# IN_12A.net
KiCad netlist of a schematic drawn in Altium Designer
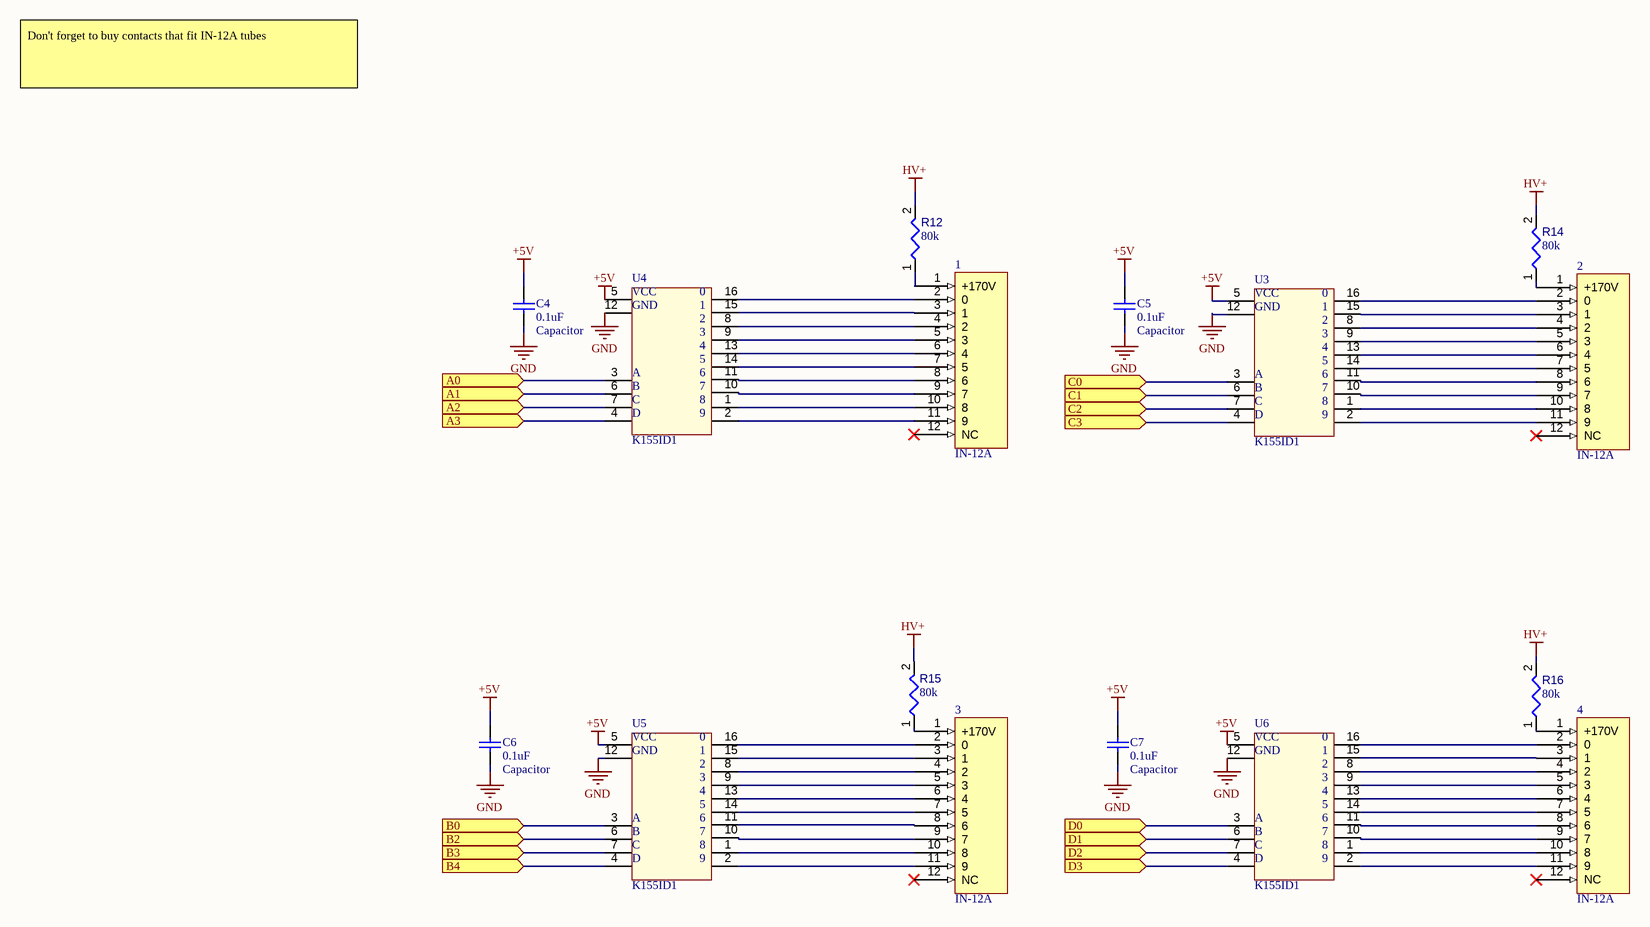
[diagram p0: IN_12A.SchDoc]

(export (version "E")
  (design (tool "Eeschema 10.0.6"))
  (components
    (comp (ref "1") (value "IN-12A") (footprint "IN-12A") (libsource (lib "HV_LIB") (part "IN-12A")))
    (comp (ref "2") (value "IN-12A") (footprint "IN-12A") (libsource (lib "HV_LIB") (part "IN-12A")))
    (comp (ref "3") (value "IN-12A") (footprint "IN-12A") (libsource (lib "HV_LIB") (part "IN-12A")))
    (comp (ref "4") (value "IN-12A") (footprint "IN-12A") (libsource (lib "HV_LIB") (part "IN-12A")))
    (comp (ref "C4")
      (value "0.1uF")
      (footprint "FOOTPRINT-1206-GEN")
      (description "CAP CER 0.1UF 50V X7R 1206")
      (fields
        (field (name "PART NUMBER") "1276-7034-1-ND")
        (field (name "TYPE") "Capacitor")
        (field (name "Comment") "Capacitor - 0.1uF - 1206")
        (field (name "PUBLISHER") "Altium Limited")
      )
      (libsource (lib "University of California Riverside - FSAE") (part "Symbol"))
    )
    (comp (ref "C5")
      (value "0.1uF")
      (footprint "FOOTPRINT-1206-GEN")
      (description "CAP CER 0.1UF 50V X7R 1206")
      (fields
        (field (name "PART NUMBER") "1276-7034-1-ND")
        (field (name "TYPE") "Capacitor")
        (field (name "Comment") "Capacitor - 0.1uF - 1206")
        (field (name "PUBLISHER") "Altium Limited")
      )
      (libsource (lib "University of California Riverside - FSAE") (part "Symbol"))
    )
    (comp (ref "C6")
      (value "0.1uF")
      (footprint "FOOTPRINT-1206-GEN")
      (description "CAP CER 0.1UF 50V X7R 1206")
      (fields
        (field (name "PART NUMBER") "1276-7034-1-ND")
        (field (name "TYPE") "Capacitor")
        (field (name "Comment") "Capacitor - 0.1uF - 1206")
        (field (name "PUBLISHER") "Altium Limited")
      )
      (libsource (lib "University of California Riverside - FSAE") (part "Symbol"))
    )
    (comp (ref "C7")
      (value "0.1uF")
      (footprint "FOOTPRINT-1206-GEN")
      (description "CAP CER 0.1UF 50V X7R 1206")
      (fields
        (field (name "PART NUMBER") "1276-7034-1-ND")
        (field (name "TYPE") "Capacitor")
        (field (name "Comment") "Capacitor - 0.1uF - 1206")
        (field (name "PUBLISHER") "Altium Limited")
      )
      (libsource (lib "University of California Riverside - FSAE") (part "Symbol"))
    )
    (comp (ref "R12")
      (value "80k")
      (footprint "RESC3216X60X45ML15T20")
      (description "Chip Resistor, 80 KOhm, +/- 1%, 0.25 W, -55 to 155 degC, 1206 (3216 Metric)")
      (fields (field (name "POWER") "250mW") (field (name "TOLERANCE") "1%"))
      (libsource (lib "University of California Riverside - FSAE") (part "RES-2"))
    )
    (comp (ref "R14")
      (value "80k")
      (footprint "RESC3216X60X45ML15T20")
      (description "Chip Resistor, 80 KOhm, +/- 1%, 0.25 W, -55 to 155 degC, 1206 (3216 Metric)")
      (fields (field (name "POWER") "250mW") (field (name "TOLERANCE") "1%"))
      (libsource (lib "University of California Riverside - FSAE") (part "RES-2"))
    )
    (comp (ref "R15")
      (value "80k")
      (footprint "RESC3216X60X45ML15T20")
      (description "Chip Resistor, 80 KOhm, +/- 1%, 0.25 W, -55 to 155 degC, 1206 (3216 Metric)")
      (fields (field (name "POWER") "250mW") (field (name "TOLERANCE") "1%"))
      (libsource (lib "University of California Riverside - FSAE") (part "RES-2"))
    )
    (comp (ref "R16")
      (value "80k")
      (footprint "RESC3216X60X45ML15T20")
      (description "Chip Resistor, 80 KOhm, +/- 1%, 0.25 W, -55 to 155 degC, 1206 (3216 Metric)")
      (fields (field (name "POWER") "250mW") (field (name "TOLERANCE") "1%"))
      (libsource (lib "University of California Riverside - FSAE") (part "RES-2"))
    )
    (comp (ref "U3")
      (value "K155ID1")
      (footprint "Socket_DIP_16")
      (libsource (lib "HV_LIB") (part "K155ID1"))
    )
    (comp (ref "U4")
      (value "K155ID1")
      (footprint "Socket_DIP_16")
      (libsource (lib "HV_LIB") (part "K155ID1"))
    )
    (comp (ref "U5")
      (value "K155ID1")
      (footprint "Socket_DIP_16")
      (libsource (lib "HV_LIB") (part "K155ID1"))
    )
    (comp (ref "U6")
      (value "K155ID1")
      (footprint "Socket_DIP_16")
      (libsource (lib "HV_LIB") (part "K155ID1"))
    )
  )
  (nets
    (net (code "1") (name "+5V") (class "Default")
      (node (ref "C4") (pin "2") (pinfunction "2_2") (pintype "passive"))
      (node (ref "C5") (pin "2") (pinfunction "2_2") (pintype "passive"))
      (node (ref "C6") (pin "2") (pinfunction "2_2") (pintype "passive"))
      (node (ref "C7") (pin "2") (pinfunction "2_2") (pintype "passive"))
      (node (ref "U3") (pin "5") (pinfunction "5_5") (pintype "passive"))
      (node (ref "U4") (pin "5") (pinfunction "5_5") (pintype "passive"))
      (node (ref "U5") (pin "5") (pinfunction "5_5") (pintype "passive"))
      (node (ref "U6") (pin "5") (pinfunction "5_5") (pintype "passive"))
    )
    (net (code "2") (name "/A0") (class "Default")
      (node (ref "U4") (pin "3") (pinfunction "3_3") (pintype "passive"))
    )
    (net (code "3") (name "/A1") (class "Default")
      (node (ref "U4") (pin "6") (pinfunction "6_6") (pintype "passive"))
    )
    (net (code "4") (name "/A2") (class "Default")
      (node (ref "U4") (pin "7") (pinfunction "7_7") (pintype "passive"))
    )
    (net (code "5") (name "/A3") (class "Default")
      (node (ref "U4") (pin "4") (pinfunction "4_4") (pintype "passive"))
    )
    (net (code "6") (name "/B0") (class "Default")
      (node (ref "U5") (pin "3") (pinfunction "3_3") (pintype "passive"))
    )
    (net (code "7") (name "/B2") (class "Default")
      (node (ref "U5") (pin "6") (pinfunction "6_6") (pintype "passive"))
    )
    (net (code "8") (name "/B3") (class "Default")
      (node (ref "U5") (pin "7") (pinfunction "7_7") (pintype "passive"))
    )
    (net (code "9") (name "/B4") (class "Default")
      (node (ref "U5") (pin "4") (pinfunction "4_4") (pintype "passive"))
    )
    (net (code "10") (name "/C0") (class "Default")
      (node (ref "U3") (pin "3") (pinfunction "3_3") (pintype "passive"))
    )
    (net (code "11") (name "/C1") (class "Default")
      (node (ref "U3") (pin "6") (pinfunction "6_6") (pintype "passive"))
    )
    (net (code "12") (name "/C2") (class "Default")
      (node (ref "U3") (pin "7") (pinfunction "7_7") (pintype "passive"))
    )
    (net (code "13") (name "/C3") (class "Default")
      (node (ref "U3") (pin "4") (pinfunction "4_4") (pintype "passive"))
    )
    (net (code "14") (name "/D0") (class "Default")
      (node (ref "U6") (pin "3") (pinfunction "3_3") (pintype "passive"))
    )
    (net (code "15") (name "/D1") (class "Default")
      (node (ref "U6") (pin "6") (pinfunction "6_6") (pintype "passive"))
    )
    (net (code "16") (name "/D2") (class "Default")
      (node (ref "U6") (pin "7") (pinfunction "7_7") (pintype "passive"))
    )
    (net (code "17") (name "/D3") (class "Default")
      (node (ref "U6") (pin "4") (pinfunction "4_4") (pintype "passive"))
    )
    (net (code "18") (name "GND") (class "Default")
      (node (ref "C4") (pin "1") (pinfunction "1_1") (pintype "passive"))
      (node (ref "C5") (pin "1") (pinfunction "1_1") (pintype "passive"))
      (node (ref "C6") (pin "1") (pinfunction "1_1") (pintype "passive"))
      (node (ref "C7") (pin "1") (pinfunction "1_1") (pintype "passive"))
      (node (ref "U3") (pin "12") (pinfunction "12_12") (pintype "passive"))
      (node (ref "U4") (pin "12") (pinfunction "12_12") (pintype "passive"))
      (node (ref "U5") (pin "12") (pinfunction "12_12") (pintype "passive"))
      (node (ref "U6") (pin "12") (pinfunction "12_12") (pintype "passive"))
    )
    (net (code "19") (name "HV+") (class "Default")
      (node (ref "R12") (pin "2") (pinfunction "2_2") (pintype "passive"))
      (node (ref "R14") (pin "2") (pinfunction "2_2") (pintype "passive"))
      (node (ref "R15") (pin "2") (pinfunction "2_2") (pintype "passive"))
      (node (ref "R16") (pin "2") (pinfunction "2_2") (pintype "passive"))
    )
    (net (code "20") (name "Net-(1-+170V)") (class "Default")
      (node (ref "1") (pin "1") (pinfunction "+170V_1") (pintype "input"))
      (node (ref "R12") (pin "1") (pinfunction "1_1") (pintype "passive"))
    )
    (net (code "21") (name "Net-(1-0)") (class "Default")
      (node (ref "1") (pin "2") (pinfunction "0_2") (pintype "input"))
      (node (ref "U4") (pin "16") (pinfunction "16_16") (pintype "passive"))
    )
    (net (code "22") (name "Net-(1-1)") (class "Default")
      (node (ref "1") (pin "3") (pinfunction "1_3") (pintype "input"))
      (node (ref "U4") (pin "15") (pinfunction "15_15") (pintype "passive"))
    )
    (net (code "23") (name "Net-(1-2)") (class "Default")
      (node (ref "1") (pin "4") (pinfunction "2_4") (pintype "input"))
      (node (ref "U4") (pin "8") (pinfunction "8_8") (pintype "passive"))
    )
    (net (code "24") (name "Net-(1-3)") (class "Default")
      (node (ref "1") (pin "5") (pinfunction "3_5") (pintype "input"))
      (node (ref "U4") (pin "9") (pinfunction "9_9") (pintype "passive"))
    )
    (net (code "25") (name "Net-(1-4)") (class "Default")
      (node (ref "1") (pin "6") (pinfunction "4_6") (pintype "input"))
      (node (ref "U4") (pin "13") (pinfunction "13_13") (pintype "passive"))
    )
    (net (code "26") (name "Net-(1-5)") (class "Default")
      (node (ref "1") (pin "7") (pinfunction "5_7") (pintype "input"))
      (node (ref "U4") (pin "14") (pinfunction "14_14") (pintype "passive"))
    )
    (net (code "27") (name "Net-(1-6)") (class "Default")
      (node (ref "1") (pin "8") (pinfunction "6_8") (pintype "input"))
      (node (ref "U4") (pin "11") (pinfunction "11_11") (pintype "passive"))
    )
    (net (code "28") (name "Net-(1-7)") (class "Default")
      (node (ref "1") (pin "9") (pinfunction "7_9") (pintype "input"))
      (node (ref "U4") (pin "10") (pinfunction "10_10") (pintype "passive"))
    )
    (net (code "29") (name "Net-(1-8)") (class "Default")
      (node (ref "1") (pin "10") (pinfunction "8_10") (pintype "input"))
      (node (ref "U4") (pin "1") (pinfunction "1_1") (pintype "passive"))
    )
    (net (code "30") (name "Net-(1-9)") (class "Default")
      (node (ref "1") (pin "11") (pinfunction "9_11") (pintype "input"))
      (node (ref "U4") (pin "2") (pinfunction "2_2") (pintype "passive"))
    )
    (net (code "31") (name "Net-(2-+170V)") (class "Default")
      (node (ref "2") (pin "1") (pinfunction "+170V_1") (pintype "input"))
      (node (ref "R14") (pin "1") (pinfunction "1_1") (pintype "passive"))
    )
    (net (code "32") (name "Net-(2-0)") (class "Default")
      (node (ref "2") (pin "2") (pinfunction "0_2") (pintype "input"))
      (node (ref "U3") (pin "16") (pinfunction "16_16") (pintype "passive"))
    )
    (net (code "33") (name "Net-(2-1)") (class "Default")
      (node (ref "2") (pin "3") (pinfunction "1_3") (pintype "input"))
      (node (ref "U3") (pin "15") (pinfunction "15_15") (pintype "passive"))
    )
    (net (code "34") (name "Net-(2-2)") (class "Default")
      (node (ref "2") (pin "4") (pinfunction "2_4") (pintype "input"))
      (node (ref "U3") (pin "8") (pinfunction "8_8") (pintype "passive"))
    )
    (net (code "35") (name "Net-(2-3)") (class "Default")
      (node (ref "2") (pin "5") (pinfunction "3_5") (pintype "input"))
      (node (ref "U3") (pin "9") (pinfunction "9_9") (pintype "passive"))
    )
    (net (code "36") (name "Net-(2-4)") (class "Default")
      (node (ref "2") (pin "6") (pinfunction "4_6") (pintype "input"))
      (node (ref "U3") (pin "13") (pinfunction "13_13") (pintype "passive"))
    )
    (net (code "37") (name "Net-(2-5)") (class "Default")
      (node (ref "2") (pin "7") (pinfunction "5_7") (pintype "input"))
      (node (ref "U3") (pin "14") (pinfunction "14_14") (pintype "passive"))
    )
    (net (code "38") (name "Net-(2-6)") (class "Default")
      (node (ref "2") (pin "8") (pinfunction "6_8") (pintype "input"))
      (node (ref "U3") (pin "11") (pinfunction "11_11") (pintype "passive"))
    )
    (net (code "39") (name "Net-(2-7)") (class "Default")
      (node (ref "2") (pin "9") (pinfunction "7_9") (pintype "input"))
      (node (ref "U3") (pin "10") (pinfunction "10_10") (pintype "passive"))
    )
    (net (code "40") (name "Net-(2-8)") (class "Default")
      (node (ref "2") (pin "10") (pinfunction "8_10") (pintype "input"))
      (node (ref "U3") (pin "1") (pinfunction "1_1") (pintype "passive"))
    )
    (net (code "41") (name "Net-(2-9)") (class "Default")
      (node (ref "2") (pin "11") (pinfunction "9_11") (pintype "input"))
      (node (ref "U3") (pin "2") (pinfunction "2_2") (pintype "passive"))
    )
    (net (code "42") (name "Net-(3-+170V)") (class "Default")
      (node (ref "3") (pin "1") (pinfunction "+170V_1") (pintype "input"))
      (node (ref "R15") (pin "1") (pinfunction "1_1") (pintype "passive"))
    )
    (net (code "43") (name "Net-(3-0)") (class "Default")
      (node (ref "3") (pin "2") (pinfunction "0_2") (pintype "input"))
      (node (ref "U5") (pin "16") (pinfunction "16_16") (pintype "passive"))
    )
    (net (code "44") (name "Net-(3-1)") (class "Default")
      (node (ref "3") (pin "3") (pinfunction "1_3") (pintype "input"))
      (node (ref "U5") (pin "15") (pinfunction "15_15") (pintype "passive"))
    )
    (net (code "45") (name "Net-(3-2)") (class "Default")
      (node (ref "3") (pin "4") (pinfunction "2_4") (pintype "input"))
      (node (ref "U5") (pin "8") (pinfunction "8_8") (pintype "passive"))
    )
    (net (code "46") (name "Net-(3-3)") (class "Default")
      (node (ref "3") (pin "5") (pinfunction "3_5") (pintype "input"))
      (node (ref "U5") (pin "9") (pinfunction "9_9") (pintype "passive"))
    )
    (net (code "47") (name "Net-(3-4)") (class "Default")
      (node (ref "3") (pin "6") (pinfunction "4_6") (pintype "input"))
      (node (ref "U5") (pin "13") (pinfunction "13_13") (pintype "passive"))
    )
    (net (code "48") (name "Net-(3-5)") (class "Default")
      (node (ref "3") (pin "7") (pinfunction "5_7") (pintype "input"))
      (node (ref "U5") (pin "14") (pinfunction "14_14") (pintype "passive"))
    )
    (net (code "49") (name "Net-(3-6)") (class "Default")
      (node (ref "3") (pin "8") (pinfunction "6_8") (pintype "input"))
      (node (ref "U5") (pin "11") (pinfunction "11_11") (pintype "passive"))
    )
    (net (code "50") (name "Net-(3-7)") (class "Default")
      (node (ref "3") (pin "9") (pinfunction "7_9") (pintype "input"))
      (node (ref "U5") (pin "10") (pinfunction "10_10") (pintype "passive"))
    )
    (net (code "51") (name "Net-(3-8)") (class "Default")
      (node (ref "3") (pin "10") (pinfunction "8_10") (pintype "input"))
      (node (ref "U5") (pin "1") (pinfunction "1_1") (pintype "passive"))
    )
    (net (code "52") (name "Net-(3-9)") (class "Default")
      (node (ref "3") (pin "11") (pinfunction "9_11") (pintype "input"))
      (node (ref "U5") (pin "2") (pinfunction "2_2") (pintype "passive"))
    )
    (net (code "53") (name "Net-(4-+170V)") (class "Default")
      (node (ref "4") (pin "1") (pinfunction "+170V_1") (pintype "input"))
      (node (ref "R16") (pin "1") (pinfunction "1_1") (pintype "passive"))
    )
    (net (code "54") (name "Net-(4-0)") (class "Default")
      (node (ref "4") (pin "2") (pinfunction "0_2") (pintype "input"))
      (node (ref "U6") (pin "16") (pinfunction "16_16") (pintype "passive"))
    )
    (net (code "55") (name "Net-(4-1)") (class "Default")
      (node (ref "4") (pin "3") (pinfunction "1_3") (pintype "input"))
      (node (ref "U6") (pin "15") (pinfunction "15_15") (pintype "passive"))
    )
    (net (code "56") (name "Net-(4-2)") (class "Default")
      (node (ref "4") (pin "4") (pinfunction "2_4") (pintype "input"))
      (node (ref "U6") (pin "8") (pinfunction "8_8") (pintype "passive"))
    )
    (net (code "57") (name "Net-(4-3)") (class "Default")
      (node (ref "4") (pin "5") (pinfunction "3_5") (pintype "input"))
      (node (ref "U6") (pin "9") (pinfunction "9_9") (pintype "passive"))
    )
    (net (code "58") (name "Net-(4-4)") (class "Default")
      (node (ref "4") (pin "6") (pinfunction "4_6") (pintype "input"))
      (node (ref "U6") (pin "13") (pinfunction "13_13") (pintype "passive"))
    )
    (net (code "59") (name "Net-(4-5)") (class "Default")
      (node (ref "4") (pin "7") (pinfunction "5_7") (pintype "input"))
      (node (ref "U6") (pin "14") (pinfunction "14_14") (pintype "passive"))
    )
    (net (code "60") (name "Net-(4-6)") (class "Default")
      (node (ref "4") (pin "8") (pinfunction "6_8") (pintype "input"))
      (node (ref "U6") (pin "11") (pinfunction "11_11") (pintype "passive"))
    )
    (net (code "61") (name "Net-(4-7)") (class "Default")
      (node (ref "4") (pin "9") (pinfunction "7_9") (pintype "input"))
      (node (ref "U6") (pin "10") (pinfunction "10_10") (pintype "passive"))
    )
    (net (code "62") (name "Net-(4-8)") (class "Default")
      (node (ref "4") (pin "10") (pinfunction "8_10") (pintype "input"))
      (node (ref "U6") (pin "1") (pinfunction "1_1") (pintype "passive"))
    )
    (net (code "63") (name "Net-(4-9)") (class "Default")
      (node (ref "4") (pin "11") (pinfunction "9_11") (pintype "input"))
      (node (ref "U6") (pin "2") (pinfunction "2_2") (pintype "passive"))
    )
    (net (code "64") (name "unconnected-(1-NC-Pad12)") (class "Default")
      (node (ref "1") (pin "12") (pinfunction "NC_12") (pintype "input+no_connect"))
    )
    (net (code "65") (name "unconnected-(2-NC-Pad12)") (class "Default")
      (node (ref "2") (pin "12") (pinfunction "NC_12") (pintype "input+no_connect"))
    )
    (net (code "66") (name "unconnected-(3-NC-Pad12)") (class "Default")
      (node (ref "3") (pin "12") (pinfunction "NC_12") (pintype "input+no_connect"))
    )
    (net (code "67") (name "unconnected-(4-NC-Pad12)") (class "Default")
      (node (ref "4") (pin "12") (pinfunction "NC_12") (pintype "input+no_connect"))
    )
  )
)
